# AcousticSpanner.net
KiCad netlist of a schematic drawn in EAGLE
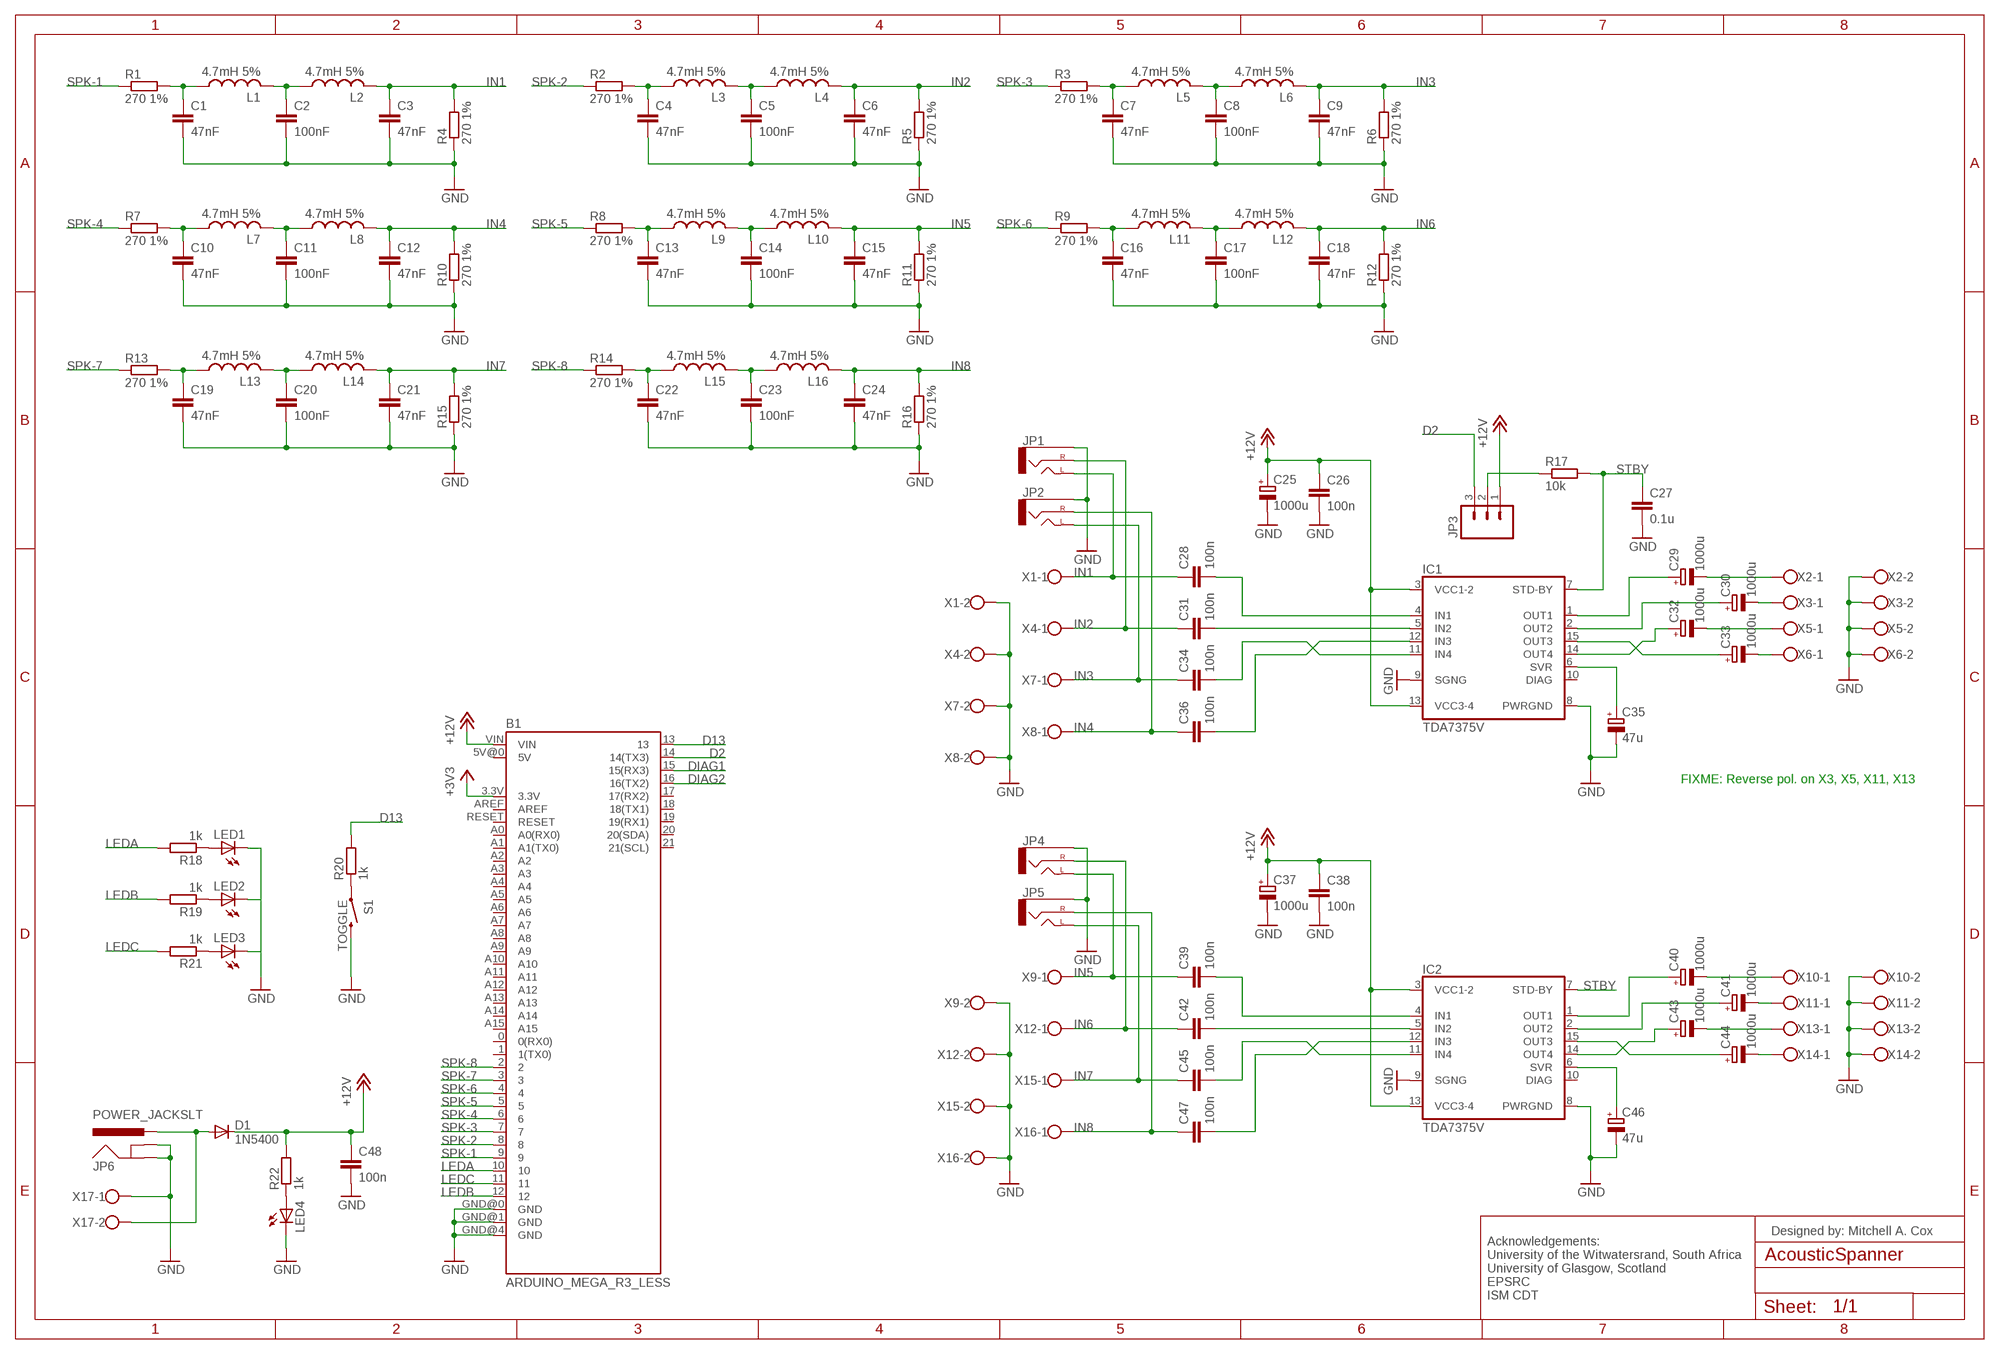
[diagram p0: schematic, sheet 1]

(export (version "E")
  (design (tool "Eeschema 10.0.6"))
  (components
    (comp (ref "B1")
      (value "ARDUINO_MEGA_R3_LESS")
      (footprint "eagle-import:ARDUINO_MEGA_LESS")
      (libsource (lib "eagle-import") (part "ARDUINO_MEGA_R3_LESS"))
    )
    (comp (ref "C1")
      (value "47nF")
      (footprint "eagle-import:C025-025X050")
      (libsource (lib "eagle-import") (part "C-EU025-025X050"))
    )
    (comp (ref "C2")
      (value "100nF")
      (footprint "eagle-import:C025-025X050")
      (libsource (lib "eagle-import") (part "C-EU025-025X050"))
    )
    (comp (ref "C3")
      (value "47nF")
      (footprint "eagle-import:C025-025X050")
      (libsource (lib "eagle-import") (part "C-EU025-025X050"))
    )
    (comp (ref "C4")
      (value "47nF")
      (footprint "eagle-import:C025-025X050")
      (libsource (lib "eagle-import") (part "C-EU025-025X050"))
    )
    (comp (ref "C5")
      (value "100nF")
      (footprint "eagle-import:C025-025X050")
      (libsource (lib "eagle-import") (part "C-EU025-025X050"))
    )
    (comp (ref "C6")
      (value "47nF")
      (footprint "eagle-import:C025-025X050")
      (libsource (lib "eagle-import") (part "C-EU025-025X050"))
    )
    (comp (ref "C7")
      (value "47nF")
      (footprint "eagle-import:C025-025X050")
      (libsource (lib "eagle-import") (part "C-EU025-025X050"))
    )
    (comp (ref "C8")
      (value "100nF")
      (footprint "eagle-import:C025-025X050")
      (libsource (lib "eagle-import") (part "C-EU025-025X050"))
    )
    (comp (ref "C9")
      (value "47nF")
      (footprint "eagle-import:C025-025X050")
      (libsource (lib "eagle-import") (part "C-EU025-025X050"))
    )
    (comp (ref "C10")
      (value "47nF")
      (footprint "eagle-import:C025-025X050")
      (libsource (lib "eagle-import") (part "C-EU025-025X050"))
    )
    (comp (ref "C11")
      (value "100nF")
      (footprint "eagle-import:C025-025X050")
      (libsource (lib "eagle-import") (part "C-EU025-025X050"))
    )
    (comp (ref "C12")
      (value "47nF")
      (footprint "eagle-import:C025-025X050")
      (libsource (lib "eagle-import") (part "C-EU025-025X050"))
    )
    (comp (ref "C13")
      (value "47nF")
      (footprint "eagle-import:C025-025X050")
      (libsource (lib "eagle-import") (part "C-EU025-025X050"))
    )
    (comp (ref "C14")
      (value "100nF")
      (footprint "eagle-import:C025-025X050")
      (libsource (lib "eagle-import") (part "C-EU025-025X050"))
    )
    (comp (ref "C15")
      (value "47nF")
      (footprint "eagle-import:C025-025X050")
      (libsource (lib "eagle-import") (part "C-EU025-025X050"))
    )
    (comp (ref "C16")
      (value "47nF")
      (footprint "eagle-import:C025-025X050")
      (libsource (lib "eagle-import") (part "C-EU025-025X050"))
    )
    (comp (ref "C17")
      (value "100nF")
      (footprint "eagle-import:C025-025X050")
      (libsource (lib "eagle-import") (part "C-EU025-025X050"))
    )
    (comp (ref "C18")
      (value "47nF")
      (footprint "eagle-import:C025-025X050")
      (libsource (lib "eagle-import") (part "C-EU025-025X050"))
    )
    (comp (ref "C19")
      (value "47nF")
      (footprint "eagle-import:C025-025X050")
      (libsource (lib "eagle-import") (part "C-EU025-025X050"))
    )
    (comp (ref "C20")
      (value "100nF")
      (footprint "eagle-import:C025-025X050")
      (libsource (lib "eagle-import") (part "C-EU025-025X050"))
    )
    (comp (ref "C21")
      (value "47nF")
      (footprint "eagle-import:C025-025X050")
      (libsource (lib "eagle-import") (part "C-EU025-025X050"))
    )
    (comp (ref "C22")
      (value "47nF")
      (footprint "eagle-import:C025-025X050")
      (libsource (lib "eagle-import") (part "C-EU025-025X050"))
    )
    (comp (ref "C23")
      (value "100nF")
      (footprint "eagle-import:C025-025X050")
      (libsource (lib "eagle-import") (part "C-EU025-025X050"))
    )
    (comp (ref "C24")
      (value "47nF")
      (footprint "eagle-import:C025-025X050")
      (libsource (lib "eagle-import") (part "C-EU025-025X050"))
    )
    (comp (ref "C25")
      (value "1000u")
      (footprint "eagle-import:E5-10,5")
      (libsource (lib "eagle-import") (part "CPOL-EUE5-10.5"))
    )
    (comp (ref "C26")
      (value "100n")
      (footprint "eagle-import:C025-025X050")
      (libsource (lib "eagle-import") (part "C-EU025-025X050"))
    )
    (comp (ref "C27")
      (value "0.1u")
      (footprint "eagle-import:C025-025X050")
      (libsource (lib "eagle-import") (part "C-EU025-025X050"))
    )
    (comp (ref "C28")
      (value "100n")
      (footprint "eagle-import:C025-025X050")
      (libsource (lib "eagle-import") (part "C-EU025-025X050"))
    )
    (comp (ref "C29")
      (value "1000u")
      (footprint "eagle-import:E5-10,5")
      (libsource (lib "eagle-import") (part "CPOL-EUE5-10.5"))
    )
    (comp (ref "C30")
      (value "1000u")
      (footprint "eagle-import:E5-10,5")
      (libsource (lib "eagle-import") (part "CPOL-EUE5-10.5"))
    )
    (comp (ref "C31")
      (value "100n")
      (footprint "eagle-import:C025-025X050")
      (libsource (lib "eagle-import") (part "C-EU025-025X050"))
    )
    (comp (ref "C32")
      (value "1000u")
      (footprint "eagle-import:E5-10,5")
      (libsource (lib "eagle-import") (part "CPOL-EUE5-10.5"))
    )
    (comp (ref "C33")
      (value "1000u")
      (footprint "eagle-import:E5-10,5")
      (libsource (lib "eagle-import") (part "CPOL-EUE5-10.5"))
    )
    (comp (ref "C34")
      (value "100n")
      (footprint "eagle-import:C025-025X050")
      (libsource (lib "eagle-import") (part "C-EU025-025X050"))
    )
    (comp (ref "C35")
      (value "47u")
      (footprint "eagle-import:E2,5-5")
      (libsource (lib "eagle-import") (part "CPOL-EUE2.5-5"))
    )
    (comp (ref "C36")
      (value "100n")
      (footprint "eagle-import:C025-025X050")
      (libsource (lib "eagle-import") (part "C-EU025-025X050"))
    )
    (comp (ref "C37")
      (value "1000u")
      (footprint "eagle-import:E5-10,5")
      (libsource (lib "eagle-import") (part "CPOL-EUE5-10.5"))
    )
    (comp (ref "C38")
      (value "100n")
      (footprint "eagle-import:C025-025X050")
      (libsource (lib "eagle-import") (part "C-EU025-025X050"))
    )
    (comp (ref "C39")
      (value "100n")
      (footprint "eagle-import:C025-025X050")
      (libsource (lib "eagle-import") (part "C-EU025-025X050"))
    )
    (comp (ref "C40")
      (value "1000u")
      (footprint "eagle-import:E5-10,5")
      (libsource (lib "eagle-import") (part "CPOL-EUE5-10.5"))
    )
    (comp (ref "C41")
      (value "1000u")
      (footprint "eagle-import:E5-10,5")
      (libsource (lib "eagle-import") (part "CPOL-EUE5-10.5"))
    )
    (comp (ref "C42")
      (value "100n")
      (footprint "eagle-import:C025-025X050")
      (libsource (lib "eagle-import") (part "C-EU025-025X050"))
    )
    (comp (ref "C43")
      (value "1000u")
      (footprint "eagle-import:E5-10,5")
      (libsource (lib "eagle-import") (part "CPOL-EUE5-10.5"))
    )
    (comp (ref "C44")
      (value "1000u")
      (footprint "eagle-import:E5-10,5")
      (libsource (lib "eagle-import") (part "CPOL-EUE5-10.5"))
    )
    (comp (ref "C45")
      (value "100n")
      (footprint "eagle-import:C025-025X050")
      (libsource (lib "eagle-import") (part "C-EU025-025X050"))
    )
    (comp (ref "C46")
      (value "47u")
      (footprint "eagle-import:E2,5-5")
      (libsource (lib "eagle-import") (part "CPOL-EUE2.5-5"))
    )
    (comp (ref "C47")
      (value "100n")
      (footprint "eagle-import:C025-025X050")
      (libsource (lib "eagle-import") (part "C-EU025-025X050"))
    )
    (comp (ref "C48")
      (value "100n")
      (footprint "eagle-import:C025-025X050")
      (libsource (lib "eagle-import") (part "C-EU025-025X050"))
    )
    (comp (ref "D1")
      (value "1N5400")
      (footprint "eagle-import:DO201-15")
      (libsource (lib "eagle-import") (part "1N5400"))
    )
    (comp (ref "IC1")
      (value "TDA7375V")
      (footprint "eagle-import:MULTIWATT-15V")
      (libsource (lib "eagle-import") (part "TDA7375V"))
    )
    (comp (ref "IC2")
      (value "TDA7375V")
      (footprint "eagle-import:MULTIWATT-15V")
      (libsource (lib "eagle-import") (part "TDA7375V"))
    )
    (comp (ref "JP1")
      (value "AUDIO-JACKPTH")
      (footprint "eagle-import:AUDIO-JACK")
      (libsource (lib "eagle-import") (part "AUDIO-JACKPTH"))
    )
    (comp (ref "JP2")
      (value "AUDIO-JACKPTH")
      (footprint "eagle-import:AUDIO-JACK")
      (libsource (lib "eagle-import") (part "AUDIO-JACKPTH"))
    )
    (comp (ref "JP3")
      (value "M03LOCK")
      (footprint "eagle-import:1X03_LOCK")
      (libsource (lib "eagle-import") (part "M03LOCK"))
    )
    (comp (ref "JP4")
      (value "AUDIO-JACKPTH")
      (footprint "eagle-import:AUDIO-JACK")
      (libsource (lib "eagle-import") (part "AUDIO-JACKPTH"))
    )
    (comp (ref "JP5")
      (value "AUDIO-JACKPTH")
      (footprint "eagle-import:AUDIO-JACK")
      (libsource (lib "eagle-import") (part "AUDIO-JACKPTH"))
    )
    (comp (ref "JP6")
      (value "POWER_JACKSLT")
      (footprint "eagle-import:POWER_JACK_SLOT")
      (libsource (lib "eagle-import") (part "POWER_JACKSLT"))
    )
    (comp (ref "L1")
      (value "4.7mH 5%")
      (footprint "eagle-import:0207_2V")
      (libsource (lib "eagle-import") (part "L-US0207/2V"))
    )
    (comp (ref "L2")
      (value "4.7mH 5%")
      (footprint "eagle-import:0207_2V")
      (libsource (lib "eagle-import") (part "L-US0207/2V"))
    )
    (comp (ref "L3")
      (value "4.7mH 5%")
      (footprint "eagle-import:0207_2V")
      (libsource (lib "eagle-import") (part "L-US0207/2V"))
    )
    (comp (ref "L4")
      (value "4.7mH 5%")
      (footprint "eagle-import:0207_2V")
      (libsource (lib "eagle-import") (part "L-US0207/2V"))
    )
    (comp (ref "L5")
      (value "4.7mH 5%")
      (footprint "eagle-import:0207_2V")
      (libsource (lib "eagle-import") (part "L-US0207/2V"))
    )
    (comp (ref "L6")
      (value "4.7mH 5%")
      (footprint "eagle-import:0207_2V")
      (libsource (lib "eagle-import") (part "L-US0207/2V"))
    )
    (comp (ref "L7")
      (value "4.7mH 5%")
      (footprint "eagle-import:0207_2V")
      (libsource (lib "eagle-import") (part "L-US0207/2V"))
    )
    (comp (ref "L8")
      (value "4.7mH 5%")
      (footprint "eagle-import:0207_2V")
      (libsource (lib "eagle-import") (part "L-US0207/2V"))
    )
    (comp (ref "L9")
      (value "4.7mH 5%")
      (footprint "eagle-import:0207_2V")
      (libsource (lib "eagle-import") (part "L-US0207/2V"))
    )
    (comp (ref "L10")
      (value "4.7mH 5%")
      (footprint "eagle-import:0207_2V")
      (libsource (lib "eagle-import") (part "L-US0207/2V"))
    )
    (comp (ref "L11")
      (value "4.7mH 5%")
      (footprint "eagle-import:0207_2V")
      (libsource (lib "eagle-import") (part "L-US0207/2V"))
    )
    (comp (ref "L12")
      (value "4.7mH 5%")
      (footprint "eagle-import:0207_2V")
      (libsource (lib "eagle-import") (part "L-US0207/2V"))
    )
    (comp (ref "L13")
      (value "4.7mH 5%")
      (footprint "eagle-import:0207_2V")
      (libsource (lib "eagle-import") (part "L-US0207/2V"))
    )
    (comp (ref "L14")
      (value "4.7mH 5%")
      (footprint "eagle-import:0207_2V")
      (libsource (lib "eagle-import") (part "L-US0207/2V"))
    )
    (comp (ref "L15")
      (value "4.7mH 5%")
      (footprint "eagle-import:0207_2V")
      (libsource (lib "eagle-import") (part "L-US0207/2V"))
    )
    (comp (ref "L16")
      (value "4.7mH 5%")
      (footprint "eagle-import:0207_2V")
      (libsource (lib "eagle-import") (part "L-US0207/2V"))
    )
    (comp (ref "LED1")
      (value "LED5MM")
      (footprint "eagle-import:LED5MM")
      (libsource (lib "eagle-import") (part "LED5MM"))
    )
    (comp (ref "LED2")
      (value "LED5MM")
      (footprint "eagle-import:LED5MM")
      (libsource (lib "eagle-import") (part "LED5MM"))
    )
    (comp (ref "LED3")
      (value "LED5MM")
      (footprint "eagle-import:LED5MM")
      (libsource (lib "eagle-import") (part "LED5MM"))
    )
    (comp (ref "LED4")
      (value "LED5MM")
      (footprint "eagle-import:LED5MM")
      (libsource (lib "eagle-import") (part "LED5MM"))
    )
    (comp (ref "R1")
      (value "270 1%")
      (footprint "eagle-import:0207_2V")
      (libsource (lib "eagle-import") (part "R-EU_0207/2V"))
    )
    (comp (ref "R2")
      (value "270 1%")
      (footprint "eagle-import:0207_2V")
      (libsource (lib "eagle-import") (part "R-EU_0207/2V"))
    )
    (comp (ref "R3")
      (value "270 1%")
      (footprint "eagle-import:0207_2V")
      (libsource (lib "eagle-import") (part "R-EU_0207/2V"))
    )
    (comp (ref "R4")
      (value "270 1%")
      (footprint "eagle-import:0207_2V")
      (libsource (lib "eagle-import") (part "R-EU_0207/2V"))
    )
    (comp (ref "R5")
      (value "270 1%")
      (footprint "eagle-import:0207_2V")
      (libsource (lib "eagle-import") (part "R-EU_0207/2V"))
    )
    (comp (ref "R6")
      (value "270 1%")
      (footprint "eagle-import:0207_2V")
      (libsource (lib "eagle-import") (part "R-EU_0207/2V"))
    )
    (comp (ref "R7")
      (value "270 1%")
      (footprint "eagle-import:0207_2V")
      (libsource (lib "eagle-import") (part "R-EU_0207/2V"))
    )
    (comp (ref "R8")
      (value "270 1%")
      (footprint "eagle-import:0207_2V")
      (libsource (lib "eagle-import") (part "R-EU_0207/2V"))
    )
    (comp (ref "R9")
      (value "270 1%")
      (footprint "eagle-import:0207_2V")
      (libsource (lib "eagle-import") (part "R-EU_0207/2V"))
    )
    (comp (ref "R10")
      (value "270 1%")
      (footprint "eagle-import:0207_2V")
      (libsource (lib "eagle-import") (part "R-EU_0207/2V"))
    )
    (comp (ref "R11")
      (value "270 1%")
      (footprint "eagle-import:0207_2V")
      (libsource (lib "eagle-import") (part "R-EU_0207/2V"))
    )
    (comp (ref "R12")
      (value "270 1%")
      (footprint "eagle-import:0207_2V")
      (libsource (lib "eagle-import") (part "R-EU_0207/2V"))
    )
    (comp (ref "R13")
      (value "270 1%")
      (footprint "eagle-import:0207_2V")
      (libsource (lib "eagle-import") (part "R-EU_0207/2V"))
    )
    (comp (ref "R14")
      (value "270 1%")
      (footprint "eagle-import:0207_2V")
      (libsource (lib "eagle-import") (part "R-EU_0207/2V"))
    )
    (comp (ref "R15")
      (value "270 1%")
      (footprint "eagle-import:0207_2V")
      (libsource (lib "eagle-import") (part "R-EU_0207/2V"))
    )
    (comp (ref "R16")
      (value "270 1%")
      (footprint "eagle-import:0207_2V")
      (libsource (lib "eagle-import") (part "R-EU_0207/2V"))
    )
    (comp (ref "R17")
      (value "10k")
      (footprint "eagle-import:0207_2V")
      (libsource (lib "eagle-import") (part "R-EU_0207/2V"))
    )
    (comp (ref "R18")
      (value "1k")
      (footprint "eagle-import:0207_2V")
      (libsource (lib "eagle-import") (part "R-EU_0207/2V"))
    )
    (comp (ref "R19")
      (value "1k")
      (footprint "eagle-import:0207_2V")
      (libsource (lib "eagle-import") (part "R-EU_0207/2V"))
    )
    (comp (ref "R20")
      (value "1k")
      (footprint "eagle-import:0207_2V")
      (libsource (lib "eagle-import") (part "R-EU_0207/2V"))
    )
    (comp (ref "R21")
      (value "1k")
      (footprint "eagle-import:0207_2V")
      (libsource (lib "eagle-import") (part "R-EU_0207/2V"))
    )
    (comp (ref "R22")
      (value "1k")
      (footprint "eagle-import:0207_2V")
      (libsource (lib "eagle-import") (part "R-EU_0207/2V"))
    )
    (comp (ref "S1")
      (value "TOGGLE")
      (footprint "eagle-import:TACTILE-PTH")
      (libsource (lib "eagle-import") (part "SWITCH-MOMENTARY-2PTH"))
    )
    (comp (ref "X1")
      (value "W237-102")
      (footprint "eagle-import:W237-102")
      (fields (field (name "MPN") "237-102"))
      (libsource (lib "eagle-import") (part "W237-102"))
    )
    (comp (ref "X2")
      (value "W237-102")
      (footprint "eagle-import:W237-102")
      (fields (field (name "MPN") "237-102"))
      (libsource (lib "eagle-import") (part "W237-102"))
    )
    (comp (ref "X3")
      (value "W237-102")
      (footprint "eagle-import:W237-102")
      (fields (field (name "MPN") "237-102"))
      (libsource (lib "eagle-import") (part "W237-102"))
    )
    (comp (ref "X4")
      (value "W237-102")
      (footprint "eagle-import:W237-102")
      (fields (field (name "MPN") "237-102"))
      (libsource (lib "eagle-import") (part "W237-102"))
    )
    (comp (ref "X5")
      (value "W237-102")
      (footprint "eagle-import:W237-102")
      (fields (field (name "MPN") "237-102"))
      (libsource (lib "eagle-import") (part "W237-102"))
    )
    (comp (ref "X6")
      (value "W237-102")
      (footprint "eagle-import:W237-102")
      (fields (field (name "MPN") "237-102"))
      (libsource (lib "eagle-import") (part "W237-102"))
    )
    (comp (ref "X7")
      (value "W237-102")
      (footprint "eagle-import:W237-102")
      (fields (field (name "MPN") "237-102"))
      (libsource (lib "eagle-import") (part "W237-102"))
    )
    (comp (ref "X8")
      (value "W237-102")
      (footprint "eagle-import:W237-102")
      (fields (field (name "MPN") "237-102"))
      (libsource (lib "eagle-import") (part "W237-102"))
    )
    (comp (ref "X9")
      (value "W237-102")
      (footprint "eagle-import:W237-102")
      (fields (field (name "MPN") "237-102"))
      (libsource (lib "eagle-import") (part "W237-102"))
    )
    (comp (ref "X10")
      (value "W237-102")
      (footprint "eagle-import:W237-102")
      (fields (field (name "MPN") "237-102"))
      (libsource (lib "eagle-import") (part "W237-102"))
    )
    (comp (ref "X11")
      (value "W237-102")
      (footprint "eagle-import:W237-102")
      (fields (field (name "MPN") "237-102"))
      (libsource (lib "eagle-import") (part "W237-102"))
    )
    (comp (ref "X12")
      (value "W237-102")
      (footprint "eagle-import:W237-102")
      (fields (field (name "MPN") "237-102"))
      (libsource (lib "eagle-import") (part "W237-102"))
    )
    (comp (ref "X13")
      (value "W237-102")
      (footprint "eagle-import:W237-102")
      (fields (field (name "MPN") "237-102"))
      (libsource (lib "eagle-import") (part "W237-102"))
    )
    (comp (ref "X14")
      (value "W237-102")
      (footprint "eagle-import:W237-102")
      (fields (field (name "MPN") "237-102"))
      (libsource (lib "eagle-import") (part "W237-102"))
    )
    (comp (ref "X15")
      (value "W237-102")
      (footprint "eagle-import:W237-102")
      (fields (field (name "MPN") "237-102"))
      (libsource (lib "eagle-import") (part "W237-102"))
    )
    (comp (ref "X16")
      (value "W237-102")
      (footprint "eagle-import:W237-102")
      (fields (field (name "MPN") "237-102"))
      (libsource (lib "eagle-import") (part "W237-102"))
    )
    (comp (ref "X17")
      (value "W237-102")
      (footprint "eagle-import:W237-102")
      (fields (field (name "MPN") "237-102"))
      (libsource (lib "eagle-import") (part "W237-102"))
    )
  )
  (nets
    (net (code "1") (name "+3V3") (class "Default")
      (node (ref "B1") (pin "3.3V") (pinfunction "3.3V_3.3V") (pintype "bidirectional"))
    )
    (net (code "2") (name "+12V") (class "Default")
      (node (ref "B1") (pin "VIN") (pinfunction "VIN_VIN") (pintype "bidirectional"))
      (node (ref "C25") (pin "+") (pinfunction "+_+") (pintype "passive"))
      (node (ref "C26") (pin "1") (pinfunction "1_1") (pintype "passive"))
      (node (ref "C37") (pin "+") (pinfunction "+_+") (pintype "passive"))
      (node (ref "C38") (pin "1") (pinfunction "1_1") (pintype "passive"))
      (node (ref "C48") (pin "1") (pinfunction "1_1") (pintype "passive"))
      (node (ref "D1") (pin "C") (pinfunction "C_C") (pintype "passive"))
      (node (ref "IC1") (pin "13") (pinfunction "VCC3-4_13") (pintype "power_in"))
      (node (ref "IC1") (pin "3") (pinfunction "VCC1-2_3") (pintype "power_in"))
      (node (ref "IC2") (pin "13") (pinfunction "VCC3-4_13") (pintype "power_in"))
      (node (ref "IC2") (pin "3") (pinfunction "VCC1-2_3") (pintype "power_in"))
      (node (ref "JP3") (pin "1") (pinfunction "1_1") (pintype "passive"))
      (node (ref "R22") (pin "2") (pinfunction "2_2") (pintype "passive"))
    )
    (net (code "3") (name "/D2") (class "Default")
      (node (ref "B1") (pin "14") (pinfunction "14(TX3)_14") (pintype "bidirectional"))
      (node (ref "JP3") (pin "3") (pinfunction "3_3") (pintype "passive"))
    )
    (net (code "4") (name "/D13") (class "Default")
      (node (ref "B1") (pin "13") (pinfunction "13_13") (pintype "bidirectional"))
      (node (ref "R20") (pin "2") (pinfunction "2_2") (pintype "passive"))
    )
    (net (code "5") (name "/DIAG1") (class "Default")
      (node (ref "B1") (pin "15") (pinfunction "15(RX3)_15") (pintype "bidirectional"))
    )
    (net (code "6") (name "/DIAG2") (class "Default")
      (node (ref "B1") (pin "16") (pinfunction "16(TX2)_16") (pintype "bidirectional"))
    )
    (net (code "7") (name "/IN1") (class "Default")
      (node (ref "C28") (pin "1") (pinfunction "1_1") (pintype "passive"))
      (node (ref "C3") (pin "1") (pinfunction "1_1") (pintype "passive"))
      (node (ref "JP1") (pin "TIP") (pinfunction "LEFT_TIP") (pintype "bidirectional"))
      (node (ref "L2") (pin "2") (pinfunction "2_2") (pintype "passive"))
      (node (ref "R4") (pin "2") (pinfunction "2_2") (pintype "passive"))
      (node (ref "X1") (pin "1") (pinfunction "KL_1") (pintype "passive"))
    )
    (net (code "8") (name "/IN2") (class "Default")
      (node (ref "C31") (pin "1") (pinfunction "1_1") (pintype "passive"))
      (node (ref "C6") (pin "1") (pinfunction "1_1") (pintype "passive"))
      (node (ref "JP1") (pin "RING") (pinfunction "RIGHT_RING") (pintype "bidirectional"))
      (node (ref "L4") (pin "2") (pinfunction "2_2") (pintype "passive"))
      (node (ref "R5") (pin "2") (pinfunction "2_2") (pintype "passive"))
      (node (ref "X4") (pin "1") (pinfunction "KL_1") (pintype "passive"))
    )
    (net (code "9") (name "/IN3") (class "Default")
      (node (ref "C34") (pin "1") (pinfunction "1_1") (pintype "passive"))
      (node (ref "C9") (pin "1") (pinfunction "1_1") (pintype "passive"))
      (node (ref "JP2") (pin "TIP") (pinfunction "LEFT_TIP") (pintype "bidirectional"))
      (node (ref "L6") (pin "2") (pinfunction "2_2") (pintype "passive"))
      (node (ref "R6") (pin "2") (pinfunction "2_2") (pintype "passive"))
      (node (ref "X7") (pin "1") (pinfunction "KL_1") (pintype "passive"))
    )
    (net (code "10") (name "/IN4") (class "Default")
      (node (ref "C12") (pin "1") (pinfunction "1_1") (pintype "passive"))
      (node (ref "C36") (pin "1") (pinfunction "1_1") (pintype "passive"))
      (node (ref "JP2") (pin "RING") (pinfunction "RIGHT_RING") (pintype "bidirectional"))
      (node (ref "L8") (pin "2") (pinfunction "2_2") (pintype "passive"))
      (node (ref "R10") (pin "2") (pinfunction "2_2") (pintype "passive"))
      (node (ref "X8") (pin "1") (pinfunction "KL_1") (pintype "passive"))
    )
    (net (code "11") (name "/IN5") (class "Default")
      (node (ref "C15") (pin "1") (pinfunction "1_1") (pintype "passive"))
      (node (ref "C39") (pin "1") (pinfunction "1_1") (pintype "passive"))
      (node (ref "JP4") (pin "TIP") (pinfunction "LEFT_TIP") (pintype "bidirectional"))
      (node (ref "L10") (pin "2") (pinfunction "2_2") (pintype "passive"))
      (node (ref "R11") (pin "2") (pinfunction "2_2") (pintype "passive"))
      (node (ref "X9") (pin "1") (pinfunction "KL_1") (pintype "passive"))
    )
    (net (code "12") (name "/IN6") (class "Default")
      (node (ref "C18") (pin "1") (pinfunction "1_1") (pintype "passive"))
      (node (ref "C42") (pin "1") (pinfunction "1_1") (pintype "passive"))
      (node (ref "JP4") (pin "RING") (pinfunction "RIGHT_RING") (pintype "bidirectional"))
      (node (ref "L12") (pin "2") (pinfunction "2_2") (pintype "passive"))
      (node (ref "R12") (pin "2") (pinfunction "2_2") (pintype "passive"))
      (node (ref "X12") (pin "1") (pinfunction "KL_1") (pintype "passive"))
    )
    (net (code "13") (name "/IN7") (class "Default")
      (node (ref "C21") (pin "1") (pinfunction "1_1") (pintype "passive"))
      (node (ref "C45") (pin "1") (pinfunction "1_1") (pintype "passive"))
      (node (ref "JP5") (pin "TIP") (pinfunction "LEFT_TIP") (pintype "bidirectional"))
      (node (ref "L14") (pin "2") (pinfunction "2_2") (pintype "passive"))
      (node (ref "R15") (pin "2") (pinfunction "2_2") (pintype "passive"))
      (node (ref "X15") (pin "1") (pinfunction "KL_1") (pintype "passive"))
    )
    (net (code "14") (name "/IN8") (class "Default")
      (node (ref "C24") (pin "1") (pinfunction "1_1") (pintype "passive"))
      (node (ref "C47") (pin "1") (pinfunction "1_1") (pintype "passive"))
      (node (ref "JP5") (pin "RING") (pinfunction "RIGHT_RING") (pintype "bidirectional"))
      (node (ref "L16") (pin "2") (pinfunction "2_2") (pintype "passive"))
      (node (ref "R16") (pin "2") (pinfunction "2_2") (pintype "passive"))
      (node (ref "X16") (pin "1") (pinfunction "KL_1") (pintype "passive"))
    )
    (net (code "15") (name "/LEDA") (class "Default")
      (node (ref "B1") (pin "10") (pinfunction "10_10") (pintype "bidirectional"))
      (node (ref "R18") (pin "2") (pinfunction "2_2") (pintype "passive"))
    )
    (net (code "16") (name "/LEDB") (class "Default")
      (node (ref "B1") (pin "12") (pinfunction "12_12") (pintype "bidirectional"))
      (node (ref "R19") (pin "2") (pinfunction "2_2") (pintype "passive"))
    )
    (net (code "17") (name "/LEDC") (class "Default")
      (node (ref "B1") (pin "11") (pinfunction "11_11") (pintype "bidirectional"))
      (node (ref "R21") (pin "2") (pinfunction "2_2") (pintype "passive"))
    )
    (net (code "18") (name "/SPK-1") (class "Default")
      (node (ref "B1") (pin "9") (pinfunction "9_9") (pintype "bidirectional"))
      (node (ref "R1") (pin "1") (pinfunction "1_1") (pintype "passive"))
    )
    (net (code "19") (name "/SPK-2") (class "Default")
      (node (ref "B1") (pin "8") (pinfunction "8_8") (pintype "bidirectional"))
      (node (ref "R2") (pin "1") (pinfunction "1_1") (pintype "passive"))
    )
    (net (code "20") (name "/SPK-3") (class "Default")
      (node (ref "B1") (pin "7") (pinfunction "7_7") (pintype "bidirectional"))
      (node (ref "R3") (pin "1") (pinfunction "1_1") (pintype "passive"))
    )
    (net (code "21") (name "/SPK-4") (class "Default")
      (node (ref "B1") (pin "6") (pinfunction "6_6") (pintype "bidirectional"))
      (node (ref "R7") (pin "1") (pinfunction "1_1") (pintype "passive"))
    )
    (net (code "22") (name "/SPK-5") (class "Default")
      (node (ref "B1") (pin "5") (pinfunction "5_5") (pintype "bidirectional"))
      (node (ref "R8") (pin "1") (pinfunction "1_1") (pintype "passive"))
    )
    (net (code "23") (name "/SPK-6") (class "Default")
      (node (ref "B1") (pin "4") (pinfunction "4_4") (pintype "bidirectional"))
      (node (ref "R9") (pin "1") (pinfunction "1_1") (pintype "passive"))
    )
    (net (code "24") (name "/SPK-7") (class "Default")
      (node (ref "B1") (pin "3") (pinfunction "3_3") (pintype "bidirectional"))
      (node (ref "R13") (pin "1") (pinfunction "1_1") (pintype "passive"))
    )
    (net (code "25") (name "/SPK-8") (class "Default")
      (node (ref "B1") (pin "2") (pinfunction "2_2") (pintype "bidirectional"))
      (node (ref "R14") (pin "1") (pinfunction "1_1") (pintype "passive"))
    )
    (net (code "26") (name "/STBY") (class "Default")
      (node (ref "C27") (pin "1") (pinfunction "1_1") (pintype "passive"))
      (node (ref "IC1") (pin "7") (pinfunction "STD-BY_7") (pintype "input"))
      (node (ref "IC2") (pin "7") (pinfunction "STD-BY_7") (pintype "input"))
      (node (ref "R17") (pin "2") (pinfunction "2_2") (pintype "passive"))
    )
    (net (code "27") (name "GND") (class "Default")
      (node (ref "B1") (pin "GND@0") (pinfunction "GND_GND@0") (pintype "bidirectional"))
      (node (ref "B1") (pin "GND@1") (pinfunction "GND_GND@1") (pintype "bidirectional"))
      (node (ref "B1") (pin "GND@4") (pinfunction "GND_GND@4") (pintype "bidirectional"))
      (node (ref "C1") (pin "2") (pinfunction "2_2") (pintype "passive"))
      (node (ref "C10") (pin "2") (pinfunction "2_2") (pintype "passive"))
      (node (ref "C11") (pin "2") (pinfunction "2_2") (pintype "passive"))
      (node (ref "C12") (pin "2") (pinfunction "2_2") (pintype "passive"))
      (node (ref "C13") (pin "2") (pinfunction "2_2") (pintype "passive"))
      (node (ref "C14") (pin "2") (pinfunction "2_2") (pintype "passive"))
      (node (ref "C15") (pin "2") (pinfunction "2_2") (pintype "passive"))
      (node (ref "C16") (pin "2") (pinfunction "2_2") (pintype "passive"))
      (node (ref "C17") (pin "2") (pinfunction "2_2") (pintype "passive"))
      (node (ref "C18") (pin "2") (pinfunction "2_2") (pintype "passive"))
      (node (ref "C19") (pin "2") (pinfunction "2_2") (pintype "passive"))
      (node (ref "C2") (pin "2") (pinfunction "2_2") (pintype "passive"))
      (node (ref "C20") (pin "2") (pinfunction "2_2") (pintype "passive"))
      (node (ref "C21") (pin "2") (pinfunction "2_2") (pintype "passive"))
      (node (ref "C22") (pin "2") (pinfunction "2_2") (pintype "passive"))
      (node (ref "C23") (pin "2") (pinfunction "2_2") (pintype "passive"))
      (node (ref "C24") (pin "2") (pinfunction "2_2") (pintype "passive"))
      (node (ref "C25") (pin "-") (pinfunction "-_-") (pintype "passive"))
      (node (ref "C26") (pin "2") (pinfunction "2_2") (pintype "passive"))
      (node (ref "C27") (pin "2") (pinfunction "2_2") (pintype "passive"))
      (node (ref "C3") (pin "2") (pinfunction "2_2") (pintype "passive"))
      (node (ref "C35") (pin "-") (pinfunction "-_-") (pintype "passive"))
      (node (ref "C37") (pin "-") (pinfunction "-_-") (pintype "passive"))
      (node (ref "C38") (pin "2") (pinfunction "2_2") (pintype "passive"))
      (node (ref "C4") (pin "2") (pinfunction "2_2") (pintype "passive"))
      (node (ref "C46") (pin "-") (pinfunction "-_-") (pintype "passive"))
      (node (ref "C48") (pin "2") (pinfunction "2_2") (pintype "passive"))
      (node (ref "C5") (pin "2") (pinfunction "2_2") (pintype "passive"))
      (node (ref "C6") (pin "2") (pinfunction "2_2") (pintype "passive"))
      (node (ref "C7") (pin "2") (pinfunction "2_2") (pintype "passive"))
      (node (ref "C8") (pin "2") (pinfunction "2_2") (pintype "passive"))
      (node (ref "C9") (pin "2") (pinfunction "2_2") (pintype "passive"))
      (node (ref "IC1") (pin "8") (pinfunction "PWRGND_8") (pintype "power_in"))
      (node (ref "IC1") (pin "9") (pinfunction "SGNG_9") (pintype "power_in"))
      (node (ref "IC2") (pin "8") (pinfunction "PWRGND_8") (pintype "power_in"))
      (node (ref "IC2") (pin "9") (pinfunction "SGNG_9") (pintype "power_in"))
      (node (ref "JP1") (pin "SLEEVE") (pinfunction "SLEEVE_SLEEVE") (pintype "bidirectional"))
      (node (ref "JP2") (pin "SLEEVE") (pinfunction "SLEEVE_SLEEVE") (pintype "bidirectional"))
      (node (ref "JP4") (pin "SLEEVE") (pinfunction "SLEEVE_SLEEVE") (pintype "bidirectional"))
      (node (ref "JP5") (pin "SLEEVE") (pinfunction "SLEEVE_SLEEVE") (pintype "bidirectional"))
      (node (ref "JP6") (pin "GND@1") (pinfunction "GNDBREAK_GND@1") (pintype "bidirectional"))
      (node (ref "JP6") (pin "GND@2") (pinfunction "GND_GND@2") (pintype "bidirectional"))
      (node (ref "LED1") (pin "K") (pinfunction "C_K") (pintype "passive"))
      (node (ref "LED2") (pin "K") (pinfunction "C_K") (pintype "passive"))
      (node (ref "LED3") (pin "K") (pinfunction "C_K") (pintype "passive"))
      (node (ref "LED4") (pin "K") (pinfunction "C_K") (pintype "passive"))
      (node (ref "R10") (pin "1") (pinfunction "1_1") (pintype "passive"))
      (node (ref "R11") (pin "1") (pinfunction "1_1") (pintype "passive"))
      (node (ref "R12") (pin "1") (pinfunction "1_1") (pintype "passive"))
      (node (ref "R15") (pin "1") (pinfunction "1_1") (pintype "passive"))
      (node (ref "R16") (pin "1") (pinfunction "1_1") (pintype "passive"))
      (node (ref "R4") (pin "1") (pinfunction "1_1") (pintype "passive"))
      (node (ref "R5") (pin "1") (pinfunction "1_1") (pintype "passive"))
      (node (ref "R6") (pin "1") (pinfunction "1_1") (pintype "passive"))
      (node (ref "S1") (pin "3") (pinfunction "2_3") (pintype "passive"))
      (node (ref "X1") (pin "2") (pinfunction "KL_2") (pintype "passive"))
      (node (ref "X10") (pin "2") (pinfunction "KL_2") (pintype "passive"))
      (node (ref "X11") (pin "2") (pinfunction "KL_2") (pintype "passive"))
      (node (ref "X12") (pin "2") (pinfunction "KL_2") (pintype "passive"))
      (node (ref "X13") (pin "2") (pinfunction "KL_2") (pintype "passive"))
      (node (ref "X14") (pin "2") (pinfunction "KL_2") (pintype "passive"))
      (node (ref "X15") (pin "2") (pinfunction "KL_2") (pintype "passive"))
      (node (ref "X16") (pin "2") (pinfunction "KL_2") (pintype "passive"))
      (node (ref "X17") (pin "1") (pinfunction "KL_1") (pintype "passive"))
      (node (ref "X2") (pin "2") (pinfunction "KL_2") (pintype "passive"))
      (node (ref "X3") (pin "2") (pinfunction "KL_2") (pintype "passive"))
      (node (ref "X4") (pin "2") (pinfunction "KL_2") (pintype "passive"))
      (node (ref "X5") (pin "2") (pinfunction "KL_2") (pintype "passive"))
      (node (ref "X6") (pin "2") (pinfunction "KL_2") (pintype "passive"))
      (node (ref "X7") (pin "2") (pinfunction "KL_2") (pintype "passive"))
      (node (ref "X8") (pin "2") (pinfunction "KL_2") (pintype "passive"))
      (node (ref "X9") (pin "2") (pinfunction "KL_2") (pintype "passive"))
    )
    (net (code "28") (name "Net-(C1-Pad1)") (class "Default")
      (node (ref "C1") (pin "1") (pinfunction "1_1") (pintype "passive"))
      (node (ref "L1") (pin "1") (pinfunction "1_1") (pintype "passive"))
      (node (ref "R1") (pin "2") (pinfunction "2_2") (pintype "passive"))
    )
    (net (code "29") (name "Net-(C2-Pad1)") (class "Default")
      (node (ref "C2") (pin "1") (pinfunction "1_1") (pintype "passive"))
      (node (ref "L1") (pin "2") (pinfunction "2_2") (pintype "passive"))
      (node (ref "L2") (pin "1") (pinfunction "1_1") (pintype "passive"))
    )
    (net (code "30") (name "Net-(C4-Pad1)") (class "Default")
      (node (ref "C4") (pin "1") (pinfunction "1_1") (pintype "passive"))
      (node (ref "L3") (pin "1") (pinfunction "1_1") (pintype "passive"))
      (node (ref "R2") (pin "2") (pinfunction "2_2") (pintype "passive"))
    )
    (net (code "31") (name "Net-(C5-Pad1)") (class "Default")
      (node (ref "C5") (pin "1") (pinfunction "1_1") (pintype "passive"))
      (node (ref "L3") (pin "2") (pinfunction "2_2") (pintype "passive"))
      (node (ref "L4") (pin "1") (pinfunction "1_1") (pintype "passive"))
    )
    (net (code "32") (name "Net-(C7-Pad1)") (class "Default")
      (node (ref "C7") (pin "1") (pinfunction "1_1") (pintype "passive"))
      (node (ref "L5") (pin "1") (pinfunction "1_1") (pintype "passive"))
      (node (ref "R3") (pin "2") (pinfunction "2_2") (pintype "passive"))
    )
    (net (code "33") (name "Net-(C8-Pad1)") (class "Default")
      (node (ref "C8") (pin "1") (pinfunction "1_1") (pintype "passive"))
      (node (ref "L5") (pin "2") (pinfunction "2_2") (pintype "passive"))
      (node (ref "L6") (pin "1") (pinfunction "1_1") (pintype "passive"))
    )
    (net (code "34") (name "Net-(C10-Pad1)") (class "Default")
      (node (ref "C10") (pin "1") (pinfunction "1_1") (pintype "passive"))
      (node (ref "L7") (pin "1") (pinfunction "1_1") (pintype "passive"))
      (node (ref "R7") (pin "2") (pinfunction "2_2") (pintype "passive"))
    )
    (net (code "35") (name "Net-(C11-Pad1)") (class "Default")
      (node (ref "C11") (pin "1") (pinfunction "1_1") (pintype "passive"))
      (node (ref "L7") (pin "2") (pinfunction "2_2") (pintype "passive"))
      (node (ref "L8") (pin "1") (pinfunction "1_1") (pintype "passive"))
    )
    (net (code "36") (name "Net-(C13-Pad1)") (class "Default")
      (node (ref "C13") (pin "1") (pinfunction "1_1") (pintype "passive"))
      (node (ref "L9") (pin "1") (pinfunction "1_1") (pintype "passive"))
      (node (ref "R8") (pin "2") (pinfunction "2_2") (pintype "passive"))
    )
    (net (code "37") (name "Net-(C14-Pad1)") (class "Default")
      (node (ref "C14") (pin "1") (pinfunction "1_1") (pintype "passive"))
      (node (ref "L10") (pin "1") (pinfunction "1_1") (pintype "passive"))
      (node (ref "L9") (pin "2") (pinfunction "2_2") (pintype "passive"))
    )
    (net (code "38") (name "Net-(C16-Pad1)") (class "Default")
      (node (ref "C16") (pin "1") (pinfunction "1_1") (pintype "passive"))
      (node (ref "L11") (pin "1") (pinfunction "1_1") (pintype "passive"))
      (node (ref "R9") (pin "2") (pinfunction "2_2") (pintype "passive"))
    )
    (net (code "39") (name "Net-(C17-Pad1)") (class "Default")
      (node (ref "C17") (pin "1") (pinfunction "1_1") (pintype "passive"))
      (node (ref "L11") (pin "2") (pinfunction "2_2") (pintype "passive"))
      (node (ref "L12") (pin "1") (pinfunction "1_1") (pintype "passive"))
    )
    (net (code "40") (name "Net-(C19-Pad1)") (class "Default")
      (node (ref "C19") (pin "1") (pinfunction "1_1") (pintype "passive"))
      (node (ref "L13") (pin "1") (pinfunction "1_1") (pintype "passive"))
      (node (ref "R13") (pin "2") (pinfunction "2_2") (pintype "passive"))
    )
    (net (code "41") (name "Net-(C20-Pad1)") (class "Default")
      (node (ref "C20") (pin "1") (pinfunction "1_1") (pintype "passive"))
      (node (ref "L13") (pin "2") (pinfunction "2_2") (pintype "passive"))
      (node (ref "L14") (pin "1") (pinfunction "1_1") (pintype "passive"))
    )
    (net (code "42") (name "Net-(C22-Pad1)") (class "Default")
      (node (ref "C22") (pin "1") (pinfunction "1_1") (pintype "passive"))
      (node (ref "L15") (pin "1") (pinfunction "1_1") (pintype "passive"))
      (node (ref "R14") (pin "2") (pinfunction "2_2") (pintype "passive"))
    )
    (net (code "43") (name "Net-(C23-Pad1)") (class "Default")
      (node (ref "C23") (pin "1") (pinfunction "1_1") (pintype "passive"))
      (node (ref "L15") (pin "2") (pinfunction "2_2") (pintype "passive"))
      (node (ref "L16") (pin "1") (pinfunction "1_1") (pintype "passive"))
    )
    (net (code "44") (name "Net-(IC1-IN1)") (class "Default")
      (node (ref "C28") (pin "2") (pinfunction "2_2") (pintype "passive"))
      (node (ref "IC1") (pin "4") (pinfunction "IN1_4") (pintype "input"))
    )
    (net (code "45") (name "Net-(IC1-IN2)") (class "Default")
      (node (ref "C31") (pin "2") (pinfunction "2_2") (pintype "passive"))
      (node (ref "IC1") (pin "5") (pinfunction "IN2_5") (pintype "input"))
    )
    (net (code "46") (name "Net-(IC1-IN3)") (class "Default")
      (node (ref "C36") (pin "2") (pinfunction "2_2") (pintype "passive"))
      (node (ref "IC1") (pin "12") (pinfunction "IN3_12") (pintype "input"))
    )
    (net (code "47") (name "Net-(IC1-IN4)") (class "Default")
      (node (ref "C34") (pin "2") (pinfunction "2_2") (pintype "passive"))
      (node (ref "IC1") (pin "11") (pinfunction "IN4_11") (pintype "input"))
    )
    (net (code "48") (name "Net-(IC1-OUT1)") (class "Default")
      (node (ref "C29") (pin "+") (pinfunction "+_+") (pintype "passive"))
      (node (ref "IC1") (pin "1") (pinfunction "OUT1_1") (pintype "output"))
    )
    (net (code "49") (name "Net-(IC1-OUT2)") (class "Default")
      (node (ref "C30") (pin "+") (pinfunction "+_+") (pintype "passive"))
      (node (ref "IC1") (pin "2") (pinfunction "OUT2_2") (pintype "output"))
    )
    (net (code "50") (name "Net-(IC1-OUT3)") (class "Default")
      (node (ref "C33") (pin "+") (pinfunction "+_+") (pintype "passive"))
      (node (ref "IC1") (pin "15") (pinfunction "OUT3_15") (pintype "output"))
    )
    (net (code "51") (name "Net-(IC1-OUT4)") (class "Default")
      (node (ref "C32") (pin "+") (pinfunction "+_+") (pintype "passive"))
      (node (ref "IC1") (pin "14") (pinfunction "OUT4_14") (pintype "output"))
    )
    (net (code "52") (name "Net-(IC1-SVR)") (class "Default")
      (node (ref "C35") (pin "+") (pinfunction "+_+") (pintype "passive"))
      (node (ref "IC1") (pin "6") (pinfunction "SVR_6") (pintype "passive"))
    )
    (net (code "53") (name "Net-(IC2-IN1)") (class "Default")
      (node (ref "C39") (pin "2") (pinfunction "2_2") (pintype "passive"))
      (node (ref "IC2") (pin "4") (pinfunction "IN1_4") (pintype "input"))
    )
    (net (code "54") (name "Net-(IC2-IN2)") (class "Default")
      (node (ref "C42") (pin "2") (pinfunction "2_2") (pintype "passive"))
      (node (ref "IC2") (pin "5") (pinfunction "IN2_5") (pintype "input"))
    )
    (net (code "55") (name "Net-(IC2-IN3)") (class "Default")
      (node (ref "C47") (pin "2") (pinfunction "2_2") (pintype "passive"))
      (node (ref "IC2") (pin "12") (pinfunction "IN3_12") (pintype "input"))
    )
    (net (code "56") (name "Net-(IC2-IN4)") (class "Default")
      (node (ref "C45") (pin "2") (pinfunction "2_2") (pintype "passive"))
      (node (ref "IC2") (pin "11") (pinfunction "IN4_11") (pintype "input"))
    )
    (net (code "57") (name "Net-(IC2-OUT1)") (class "Default")
      (node (ref "C40") (pin "+") (pinfunction "+_+") (pintype "passive"))
      (node (ref "IC2") (pin "1") (pinfunction "OUT1_1") (pintype "output"))
    )
    (net (code "58") (name "Net-(IC2-OUT2)") (class "Default")
      (node (ref "C41") (pin "+") (pinfunction "+_+") (pintype "passive"))
      (node (ref "IC2") (pin "2") (pinfunction "OUT2_2") (pintype "output"))
    )
    (net (code "59") (name "Net-(IC2-OUT3)") (class "Default")
      (node (ref "C44") (pin "+") (pinfunction "+_+") (pintype "passive"))
      (node (ref "IC2") (pin "15") (pinfunction "OUT3_15") (pintype "output"))
    )
    (net (code "60") (name "Net-(IC2-OUT4)") (class "Default")
      (node (ref "C43") (pin "+") (pinfunction "+_+") (pintype "passive"))
      (node (ref "IC2") (pin "14") (pinfunction "OUT4_14") (pintype "output"))
    )
    (net (code "61") (name "Net-(IC2-SVR)") (class "Default")
      (node (ref "C46") (pin "+") (pinfunction "+_+") (pintype "passive"))
      (node (ref "IC2") (pin "6") (pinfunction "SVR_6") (pintype "passive"))
    )
    (net (code "62") (name "Net-(JP3-Pad2)") (class "Default")
      (node (ref "JP3") (pin "2") (pinfunction "2_2") (pintype "passive"))
      (node (ref "R17") (pin "1") (pinfunction "1_1") (pintype "passive"))
    )
    (net (code "63") (name "Net-(LED1-PadA)") (class "Default")
      (node (ref "LED1") (pin "A") (pinfunction "A_A") (pintype "passive"))
      (node (ref "R18") (pin "1") (pinfunction "1_1") (pintype "passive"))
    )
    (net (code "64") (name "Net-(LED2-PadA)") (class "Default")
      (node (ref "LED2") (pin "A") (pinfunction "A_A") (pintype "passive"))
      (node (ref "R19") (pin "1") (pinfunction "1_1") (pintype "passive"))
    )
    (net (code "65") (name "Net-(LED3-PadA)") (class "Default")
      (node (ref "LED3") (pin "A") (pinfunction "A_A") (pintype "passive"))
      (node (ref "R21") (pin "1") (pinfunction "1_1") (pintype "passive"))
    )
    (net (code "66") (name "Net-(LED4-PadA)") (class "Default")
      (node (ref "LED4") (pin "A") (pinfunction "A_A") (pintype "passive"))
      (node (ref "R22") (pin "1") (pinfunction "1_1") (pintype "passive"))
    )
    (net (code "67") (name "Net-(R20-Pad1)") (class "Default")
      (node (ref "R20") (pin "1") (pinfunction "1_1") (pintype "passive"))
      (node (ref "S1") (pin "1") (pinfunction "1_1") (pintype "passive"))
    )
    (net (code "68") (name "Net-(X2A-KL)") (class "Default")
      (node (ref "C29") (pin "-") (pinfunction "-_-") (pintype "passive"))
      (node (ref "X2") (pin "1") (pinfunction "KL_1") (pintype "passive"))
    )
    (net (code "69") (name "Net-(X3A-KL)") (class "Default")
      (node (ref "C30") (pin "-") (pinfunction "-_-") (pintype "passive"))
      (node (ref "X3") (pin "1") (pinfunction "KL_1") (pintype "passive"))
    )
    (net (code "70") (name "Net-(X5A-KL)") (class "Default")
      (node (ref "C32") (pin "-") (pinfunction "-_-") (pintype "passive"))
      (node (ref "X5") (pin "1") (pinfunction "KL_1") (pintype "passive"))
    )
    (net (code "71") (name "Net-(X6A-KL)") (class "Default")
      (node (ref "C33") (pin "-") (pinfunction "-_-") (pintype "passive"))
      (node (ref "X6") (pin "1") (pinfunction "KL_1") (pintype "passive"))
    )
    (net (code "72") (name "Net-(X10A-KL)") (class "Default")
      (node (ref "C40") (pin "-") (pinfunction "-_-") (pintype "passive"))
      (node (ref "X10") (pin "1") (pinfunction "KL_1") (pintype "passive"))
    )
    (net (code "73") (name "Net-(X11A-KL)") (class "Default")
      (node (ref "C41") (pin "-") (pinfunction "-_-") (pintype "passive"))
      (node (ref "X11") (pin "1") (pinfunction "KL_1") (pintype "passive"))
    )
    (net (code "74") (name "Net-(X13A-KL)") (class "Default")
      (node (ref "C43") (pin "-") (pinfunction "-_-") (pintype "passive"))
      (node (ref "X13") (pin "1") (pinfunction "KL_1") (pintype "passive"))
    )
    (net (code "75") (name "Net-(X14A-KL)") (class "Default")
      (node (ref "C44") (pin "-") (pinfunction "-_-") (pintype "passive"))
      (node (ref "X14") (pin "1") (pinfunction "KL_1") (pintype "passive"))
    )
    (net (code "76") (name "Net-(X17B-KL)") (class "Default")
      (node (ref "D1") (pin "A") (pinfunction "A_A") (pintype "passive"))
      (node (ref "JP6") (pin "PWR") (pinfunction "PWR_PWR") (pintype "bidirectional"))
      (node (ref "X17") (pin "2") (pinfunction "KL_2") (pintype "passive"))
    )
    (net (code "77") (name "unconnected-(B1-0(RX0)-Pad0)") (class "Default")
      (node (ref "B1") (pin "0") (pinfunction "0(RX0)_0") (pintype "bidirectional"))
    )
    (net (code "78") (name "unconnected-(B1-1(TX0)-Pad1)") (class "Default")
      (node (ref "B1") (pin "1") (pinfunction "1(TX0)_1") (pintype "bidirectional"))
    )
    (net (code "79") (name "unconnected-(B1-5V-Pad5V@0)") (class "Default")
      (node (ref "B1") (pin "5V@0") (pinfunction "5V_5V@0") (pintype "bidirectional"))
    )
    (net (code "80") (name "unconnected-(B1-17(RX2)-Pad17)") (class "Default")
      (node (ref "B1") (pin "17") (pinfunction "17(RX2)_17") (pintype "bidirectional"))
    )
    (net (code "81") (name "unconnected-(B1-18(TX1)-Pad18)") (class "Default")
      (node (ref "B1") (pin "18") (pinfunction "18(TX1)_18") (pintype "bidirectional"))
    )
    (net (code "82") (name "unconnected-(B1-19(RX1)-Pad19)") (class "Default")
      (node (ref "B1") (pin "19") (pinfunction "19(RX1)_19") (pintype "bidirectional"))
    )
    (net (code "83") (name "unconnected-(B1-20(SDA)-Pad20)") (class "Default")
      (node (ref "B1") (pin "20") (pinfunction "20(SDA)_20") (pintype "bidirectional"))
    )
    (net (code "84") (name "unconnected-(B1-21(SCL)-Pad21)") (class "Default")
      (node (ref "B1") (pin "21") (pinfunction "21(SCL)_21") (pintype "bidirectional"))
    )
    (net (code "85") (name "unconnected-(B1-A0(RX0)-PadA0)") (class "Default")
      (node (ref "B1") (pin "A0") (pinfunction "A0(RX0)_A0") (pintype "bidirectional"))
    )
    (net (code "86") (name "unconnected-(B1-A1(TX0)-PadA1)") (class "Default")
      (node (ref "B1") (pin "A1") (pinfunction "A1(TX0)_A1") (pintype "bidirectional"))
    )
    (net (code "87") (name "unconnected-(B1-PadA2)") (class "Default")
      (node (ref "B1") (pin "A2") (pinfunction "A2_A2") (pintype "bidirectional"))
    )
    (net (code "88") (name "unconnected-(B1-PadA3)") (class "Default")
      (node (ref "B1") (pin "A3") (pinfunction "A3_A3") (pintype "bidirectional"))
    )
    (net (code "89") (name "unconnected-(B1-PadA4)") (class "Default")
      (node (ref "B1") (pin "A4") (pinfunction "A4_A4") (pintype "bidirectional"))
    )
    (net (code "90") (name "unconnected-(B1-PadA5)") (class "Default")
      (node (ref "B1") (pin "A5") (pinfunction "A5_A5") (pintype "bidirectional"))
    )
    (net (code "91") (name "unconnected-(B1-PadA6)") (class "Default")
      (node (ref "B1") (pin "A6") (pinfunction "A6_A6") (pintype "bidirectional"))
    )
    (net (code "92") (name "unconnected-(B1-PadA7)") (class "Default")
      (node (ref "B1") (pin "A7") (pinfunction "A7_A7") (pintype "bidirectional"))
    )
    (net (code "93") (name "unconnected-(B1-PadA8)") (class "Default")
      (node (ref "B1") (pin "A8") (pinfunction "A8_A8") (pintype "bidirectional"))
    )
    (net (code "94") (name "unconnected-(B1-PadA9)") (class "Default")
      (node (ref "B1") (pin "A9") (pinfunction "A9_A9") (pintype "bidirectional"))
    )
    (net (code "95") (name "unconnected-(B1-PadA10)") (class "Default")
      (node (ref "B1") (pin "A10") (pinfunction "A10_A10") (pintype "bidirectional"))
    )
    (net (code "96") (name "unconnected-(B1-PadA11)") (class "Default")
      (node (ref "B1") (pin "A11") (pinfunction "A11_A11") (pintype "bidirectional"))
    )
    (net (code "97") (name "unconnected-(B1-PadA12)") (class "Default")
      (node (ref "B1") (pin "A12") (pinfunction "A12_A12") (pintype "bidirectional"))
    )
    (net (code "98") (name "unconnected-(B1-PadA13)") (class "Default")
      (node (ref "B1") (pin "A13") (pinfunction "A13_A13") (pintype "bidirectional"))
    )
    (net (code "99") (name "unconnected-(B1-PadA14)") (class "Default")
      (node (ref "B1") (pin "A14") (pinfunction "A14_A14") (pintype "bidirectional"))
    )
    (net (code "100") (name "unconnected-(B1-PadA15)") (class "Default")
      (node (ref "B1") (pin "A15") (pinfunction "A15_A15") (pintype "bidirectional"))
    )
    (net (code "101") (name "unconnected-(B1-PadAREF)") (class "Default")
      (node (ref "B1") (pin "AREF") (pinfunction "AREF_AREF") (pintype "bidirectional"))
    )
    (net (code "102") (name "unconnected-(B1-PadRESET)") (class "Default")
      (node (ref "B1") (pin "RESET") (pinfunction "RESET_RESET") (pintype "bidirectional"))
    )
    (net (code "103") (name "unconnected-(IC1-DIAG-Pad10)") (class "Default")
      (node (ref "IC1") (pin "10") (pinfunction "DIAG_10") (pintype "passive"))
    )
    (net (code "104") (name "unconnected-(IC2-DIAG-Pad10)") (class "Default")
      (node (ref "IC2") (pin "10") (pinfunction "DIAG_10") (pintype "passive"))
    )
  )
)
